# single_motor_improved.net
KiCad netlist of a schematic drawn in EAGLE
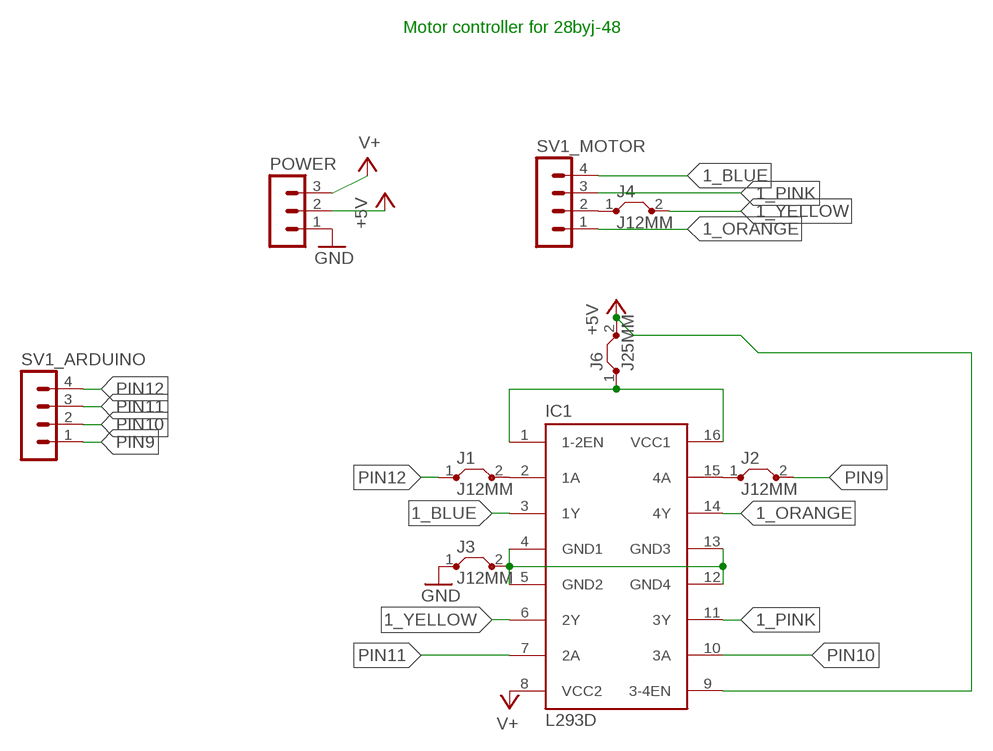
[diagram p0: schematic, sheet 1]

(export (version "E")
  (design (tool "Eeschema 10.0.6"))
  (components
    (comp (ref "IC1")
      (value "L293D")
      (footprint "eagle-import:DIL16")
      (libsource (lib "eagle-import") (part "L293D"))
    )
    (comp (ref "J1")
      (value "J12MM")
      (footprint "eagle-import:12")
      (libsource (lib "eagle-import") (part "J12MM"))
    )
    (comp (ref "J2")
      (value "J12MM")
      (footprint "eagle-import:12")
      (libsource (lib "eagle-import") (part "J12MM"))
    )
    (comp (ref "J3")
      (value "J12MM")
      (footprint "eagle-import:12")
      (libsource (lib "eagle-import") (part "J12MM"))
    )
    (comp (ref "J4")
      (value "J12MM")
      (footprint "eagle-import:12")
      (libsource (lib "eagle-import") (part "J12MM"))
    )
    (comp (ref "J6")
      (value "J25MM")
      (footprint "eagle-import:25")
      (libsource (lib "eagle-import") (part "J25MM"))
    )
    (comp (ref "POWER")
      (value "MA03-1")
      (footprint "eagle-import:MA03-1")
      (libsource (lib "eagle-import") (part "MA03-1"))
    )
    (comp (ref "SV1_ARDUINO")
      (value "MA04-1")
      (footprint "eagle-import:MA04-1")
      (libsource (lib "eagle-import") (part "MA04-1"))
    )
    (comp (ref "SV1_MOTOR")
      (value "MA04-1")
      (footprint "eagle-import:MA04-1")
      (libsource (lib "eagle-import") (part "MA04-1"))
    )
  )
  (nets
    (net (code "1") (name "+5V") (class "Default")
      (node (ref "IC1") (pin "9") (pinfunction "3-4EN_9") (pintype "input"))
      (node (ref "J6") (pin "2") (pinfunction "2_2") (pintype "passive"))
      (node (ref "POWER") (pin "2") (pinfunction "2_2") (pintype "passive"))
    )
    (net (code "2") (name "1_BLUE") (class "Default")
      (node (ref "IC1") (pin "3") (pinfunction "1Y_3") (pintype "output"))
      (node (ref "SV1_MOTOR") (pin "4") (pinfunction "4_4") (pintype "passive"))
    )
    (net (code "3") (name "1_ORANGE") (class "Default")
      (node (ref "IC1") (pin "14") (pinfunction "4Y_14") (pintype "output"))
      (node (ref "SV1_MOTOR") (pin "1") (pinfunction "1_1") (pintype "passive"))
    )
    (net (code "4") (name "1_PINK") (class "Default")
      (node (ref "IC1") (pin "11") (pinfunction "3Y_11") (pintype "output"))
      (node (ref "SV1_MOTOR") (pin "3") (pinfunction "3_3") (pintype "passive"))
    )
    (net (code "5") (name "1_YELLOW") (class "Default")
      (node (ref "IC1") (pin "6") (pinfunction "2Y_6") (pintype "output"))
      (node (ref "J4") (pin "2") (pinfunction "2_2") (pintype "passive"))
    )
    (net (code "6") (name "GND") (class "Default")
      (node (ref "J3") (pin "1") (pinfunction "1_1") (pintype "passive"))
      (node (ref "POWER") (pin "1") (pinfunction "1_1") (pintype "passive"))
    )
    (net (code "7") (name "Net-(IC1-1-2EN)") (class "Default")
      (node (ref "IC1") (pin "1") (pinfunction "1-2EN_1") (pintype "input"))
      (node (ref "IC1") (pin "16") (pinfunction "VCC1_16") (pintype "power_in"))
      (node (ref "J6") (pin "1") (pinfunction "1_1") (pintype "passive"))
    )
    (net (code "8") (name "Net-(IC1-1A)") (class "Default")
      (node (ref "IC1") (pin "2") (pinfunction "1A_2") (pintype "input"))
      (node (ref "J1") (pin "2") (pinfunction "2_2") (pintype "passive"))
    )
    (net (code "9") (name "Net-(IC1-4A)") (class "Default")
      (node (ref "IC1") (pin "15") (pinfunction "4A_15") (pintype "input"))
      (node (ref "J2") (pin "1") (pinfunction "1_1") (pintype "passive"))
    )
    (net (code "10") (name "Net-(IC1-GND1)") (class "Default")
      (node (ref "IC1") (pin "12") (pinfunction "GND4_12") (pintype "power_in"))
      (node (ref "IC1") (pin "13") (pinfunction "GND3_13") (pintype "power_in"))
      (node (ref "IC1") (pin "4") (pinfunction "GND1_4") (pintype "power_in"))
      (node (ref "IC1") (pin "5") (pinfunction "GND2_5") (pintype "power_in"))
      (node (ref "J3") (pin "2") (pinfunction "2_2") (pintype "passive"))
    )
    (net (code "11") (name "Net-(J4-Pad1)") (class "Default")
      (node (ref "J4") (pin "1") (pinfunction "1_1") (pintype "passive"))
      (node (ref "SV1_MOTOR") (pin "2") (pinfunction "2_2") (pintype "passive"))
    )
    (net (code "12") (name "PIN9") (class "Default")
      (node (ref "J2") (pin "2") (pinfunction "2_2") (pintype "passive"))
      (node (ref "SV1_ARDUINO") (pin "1") (pinfunction "1_1") (pintype "passive"))
    )
    (net (code "13") (name "PIN10") (class "Default")
      (node (ref "IC1") (pin "10") (pinfunction "3A_10") (pintype "input"))
      (node (ref "SV1_ARDUINO") (pin "2") (pinfunction "2_2") (pintype "passive"))
    )
    (net (code "14") (name "PIN11") (class "Default")
      (node (ref "IC1") (pin "7") (pinfunction "2A_7") (pintype "input"))
      (node (ref "SV1_ARDUINO") (pin "3") (pinfunction "3_3") (pintype "passive"))
    )
    (net (code "15") (name "PIN12") (class "Default")
      (node (ref "J1") (pin "1") (pinfunction "1_1") (pintype "passive"))
      (node (ref "SV1_ARDUINO") (pin "4") (pinfunction "4_4") (pintype "passive"))
    )
    (net (code "16") (name "V+") (class "Default")
      (node (ref "IC1") (pin "8") (pinfunction "VCC2_8") (pintype "power_in"))
      (node (ref "POWER") (pin "3") (pinfunction "3_3") (pintype "passive"))
    )
  )
)
